# position_sensor.net
KiCad netlist of a schematic drawn in EAGLE
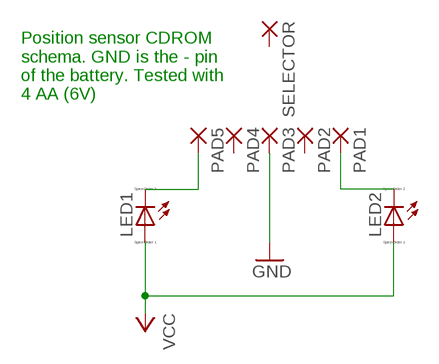
[diagram p0: schematic, sheet 1]

(export (version "E")
  (design (tool "Eeschema 10.0.6"))
  (components
    (comp (ref "LED1")
      (value "LED_ELD260")
      (footprint "eagle-import:LED_LD260")
      (libsource (lib "eagle-import") (part "LED_ELD260"))
    )
    (comp (ref "LED2")
      (value "LED_ELD260")
      (footprint "eagle-import:LED_LD260")
      (libsource (lib "eagle-import") (part "LED_ELD260"))
    )
    (comp (ref "PAD1")
      (value "SMD2")
      (footprint "eagle-import:SMD1,27-2,54")
      (libsource (lib "eagle-import") (part "SMD2"))
    )
    (comp (ref "PAD2")
      (value "SMD2")
      (footprint "eagle-import:SMD1,27-2,54")
      (libsource (lib "eagle-import") (part "SMD2"))
    )
    (comp (ref "PAD3")
      (value "SMD2")
      (footprint "eagle-import:SMD1,27-2,54")
      (libsource (lib "eagle-import") (part "SMD2"))
    )
    (comp (ref "PAD4")
      (value "SMD2")
      (footprint "eagle-import:SMD1,27-2,54")
      (libsource (lib "eagle-import") (part "SMD2"))
    )
    (comp (ref "PAD5")
      (value "SMD2")
      (footprint "eagle-import:SMD1,27-2,54")
      (libsource (lib "eagle-import") (part "SMD2"))
    )
    (comp (ref "SELECTOR")
      (value "SMD2")
      (footprint "eagle-import:SMD1,27-2,54")
      (libsource (lib "eagle-import") (part "SMD2"))
    )
  )
  (nets
    (net (code "1") (name "GND") (class "Default")
      (node (ref "PAD3") (pin "1") (pinfunction "P_1") (pintype "passive"))
    )
    (net (code "2") (name "Net-(LED1-C)") (class "Default")
      (node (ref "LED1") (pin "K") (pinfunction "C_K") (pintype "passive"))
      (node (ref "PAD5") (pin "1") (pinfunction "P_1") (pintype "passive"))
    )
    (net (code "3") (name "Net-(LED2-C)") (class "Default")
      (node (ref "LED2") (pin "K") (pinfunction "C_K") (pintype "passive"))
      (node (ref "PAD1") (pin "1") (pinfunction "P_1") (pintype "passive"))
    )
    (net (code "4") (name "VCC") (class "Default")
      (node (ref "LED1") (pin "A") (pinfunction "A_A") (pintype "passive"))
      (node (ref "LED2") (pin "A") (pinfunction "A_A") (pintype "passive"))
    )
    (net (code "5") (name "unconnected-(PAD2-P-Pad1)") (class "Default")
      (node (ref "PAD2") (pin "1") (pinfunction "P_1") (pintype "passive"))
    )
    (net (code "6") (name "unconnected-(PAD4-P-Pad1)") (class "Default")
      (node (ref "PAD4") (pin "1") (pinfunction "P_1") (pintype "passive"))
    )
    (net (code "7") (name "unconnected-(SELECTOR-P-Pad1)") (class "Default")
      (node (ref "SELECTOR") (pin "1") (pinfunction "P_1") (pintype "passive"))
    )
  )
)
